# Filter.net
KiCad netlist of a schematic drawn in Altium Designer
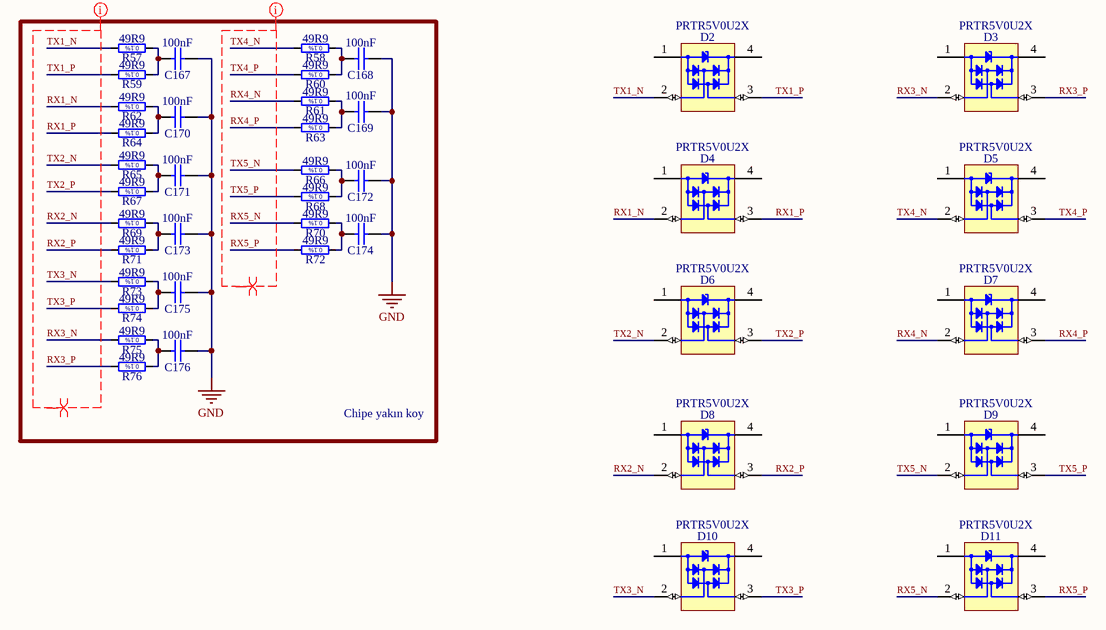
[diagram p0: Filter.SchDoc]

(export (version "E")
  (design (tool "Eeschema 10.0.6"))
  (components
    (comp (ref "C167")
      (value "100nF")
      (footprint "CAPC1608X87N")
      (description "Non-polarised capacitor")
      (fields
        (field (name "PART NUMBER") "CC0603_100NF_50V_10%_X7R")
        (field (name "VOLTAGE") "50V")
        (field (name "AUTHOR") "CERN DEM JLC")
      )
      (libsource (lib "Capacitors") (part "Capacitor - non polarized"))
    )
    (comp (ref "C168")
      (value "100nF")
      (footprint "CAPC1608X87N")
      (description "Non-polarised capacitor")
      (fields
        (field (name "PART NUMBER") "CC0603_100NF_50V_10%_X7R")
        (field (name "VOLTAGE") "50V")
        (field (name "AUTHOR") "CERN DEM JLC")
      )
      (libsource (lib "Capacitors") (part "Capacitor - non polarized"))
    )
    (comp (ref "C169")
      (value "100nF")
      (footprint "CAPC1608X87N")
      (description "Non-polarised capacitor")
      (fields
        (field (name "PART NUMBER") "CC0603_100NF_50V_10%_X7R")
        (field (name "VOLTAGE") "50V")
        (field (name "AUTHOR") "CERN DEM JLC")
      )
      (libsource (lib "Capacitors") (part "Capacitor - non polarized"))
    )
    (comp (ref "C170")
      (value "100nF")
      (footprint "CAPC1608X87N")
      (description "Non-polarised capacitor")
      (fields
        (field (name "PART NUMBER") "CC0603_100NF_50V_10%_X7R")
        (field (name "VOLTAGE") "50V")
        (field (name "AUTHOR") "CERN DEM JLC")
      )
      (libsource (lib "Capacitors") (part "Capacitor - non polarized"))
    )
    (comp (ref "C171")
      (value "100nF")
      (footprint "CAPC1608X87N")
      (description "Non-polarised capacitor")
      (fields
        (field (name "PART NUMBER") "CC0603_100NF_50V_10%_X7R")
        (field (name "VOLTAGE") "50V")
        (field (name "AUTHOR") "CERN DEM JLC")
      )
      (libsource (lib "Capacitors") (part "Capacitor - non polarized"))
    )
    (comp (ref "C172")
      (value "100nF")
      (footprint "CAPC1608X87N")
      (description "Non-polarised capacitor")
      (fields
        (field (name "PART NUMBER") "CC0603_100NF_50V_10%_X7R")
        (field (name "VOLTAGE") "50V")
        (field (name "AUTHOR") "CERN DEM JLC")
      )
      (libsource (lib "Capacitors") (part "Capacitor - non polarized"))
    )
    (comp (ref "C173")
      (value "100nF")
      (footprint "CAPC1608X87N")
      (description "Non-polarised capacitor")
      (fields
        (field (name "PART NUMBER") "CC0603_100NF_50V_10%_X7R")
        (field (name "VOLTAGE") "50V")
        (field (name "AUTHOR") "CERN DEM JLC")
      )
      (libsource (lib "Capacitors") (part "Capacitor - non polarized"))
    )
    (comp (ref "C174")
      (value "100nF")
      (footprint "CAPC1608X87N")
      (description "Non-polarised capacitor")
      (fields
        (field (name "PART NUMBER") "CC0603_100NF_50V_10%_X7R")
        (field (name "VOLTAGE") "50V")
        (field (name "AUTHOR") "CERN DEM JLC")
      )
      (libsource (lib "Capacitors") (part "Capacitor - non polarized"))
    )
    (comp (ref "C175")
      (value "100nF")
      (footprint "CAPC1608X87N")
      (description "Non-polarised capacitor")
      (fields
        (field (name "PART NUMBER") "CC0603_100NF_50V_10%_X7R")
        (field (name "VOLTAGE") "50V")
        (field (name "AUTHOR") "CERN DEM JLC")
      )
      (libsource (lib "Capacitors") (part "Capacitor - non polarized"))
    )
    (comp (ref "C176")
      (value "100nF")
      (footprint "CAPC1608X87N")
      (description "Non-polarised capacitor")
      (fields
        (field (name "PART NUMBER") "CC0603_100NF_50V_10%_X7R")
        (field (name "VOLTAGE") "50V")
        (field (name "AUTHOR") "CERN DEM JLC")
      )
      (libsource (lib "Capacitors") (part "Capacitor - non polarized"))
    )
    (comp (ref "D2")
      (value "PRTR5V0U2X")
      (footprint "SOT190P230X110-4N")
      (description "Ultra Low Capacitance Double Rail-to-Rail ESD Protection Diode")
      (fields
        (field (name "PART NUMBER") "PRTR5V0U2X")
        (field (name "VOLTAGE") "5.5V")
        (field (name "MANUFACTURER") "NXP Semiconductors")
        (field (name "AUTHOR") "CERN DEM JLC")
      )
      (libsource (lib "ICs And Semiconductors") (part "PRTR5V0U2X"))
    )
    (comp (ref "D3")
      (value "PRTR5V0U2X")
      (footprint "SOT190P230X110-4N")
      (description "Ultra Low Capacitance Double Rail-to-Rail ESD Protection Diode")
      (fields
        (field (name "PART NUMBER") "PRTR5V0U2X")
        (field (name "VOLTAGE") "5.5V")
        (field (name "MANUFACTURER") "NXP Semiconductors")
        (field (name "AUTHOR") "CERN DEM JLC")
      )
      (libsource (lib "ICs And Semiconductors") (part "PRTR5V0U2X"))
    )
    (comp (ref "D4")
      (value "PRTR5V0U2X")
      (footprint "SOT190P230X110-4N")
      (description "Ultra Low Capacitance Double Rail-to-Rail ESD Protection Diode")
      (fields
        (field (name "PART NUMBER") "PRTR5V0U2X")
        (field (name "VOLTAGE") "5.5V")
        (field (name "MANUFACTURER") "NXP Semiconductors")
        (field (name "AUTHOR") "CERN DEM JLC")
      )
      (libsource (lib "ICs And Semiconductors") (part "PRTR5V0U2X"))
    )
    (comp (ref "D5")
      (value "PRTR5V0U2X")
      (footprint "SOT190P230X110-4N")
      (description "Ultra Low Capacitance Double Rail-to-Rail ESD Protection Diode")
      (fields
        (field (name "PART NUMBER") "PRTR5V0U2X")
        (field (name "VOLTAGE") "5.5V")
        (field (name "MANUFACTURER") "NXP Semiconductors")
        (field (name "AUTHOR") "CERN DEM JLC")
      )
      (libsource (lib "ICs And Semiconductors") (part "PRTR5V0U2X"))
    )
    (comp (ref "D6")
      (value "PRTR5V0U2X")
      (footprint "SOT190P230X110-4N")
      (description "Ultra Low Capacitance Double Rail-to-Rail ESD Protection Diode")
      (fields
        (field (name "PART NUMBER") "PRTR5V0U2X")
        (field (name "VOLTAGE") "5.5V")
        (field (name "MANUFACTURER") "NXP Semiconductors")
        (field (name "AUTHOR") "CERN DEM JLC")
      )
      (libsource (lib "ICs And Semiconductors") (part "PRTR5V0U2X"))
    )
    (comp (ref "D7")
      (value "PRTR5V0U2X")
      (footprint "SOT190P230X110-4N")
      (description "Ultra Low Capacitance Double Rail-to-Rail ESD Protection Diode")
      (fields
        (field (name "PART NUMBER") "PRTR5V0U2X")
        (field (name "VOLTAGE") "5.5V")
        (field (name "MANUFACTURER") "NXP Semiconductors")
        (field (name "AUTHOR") "CERN DEM JLC")
      )
      (libsource (lib "ICs And Semiconductors") (part "PRTR5V0U2X"))
    )
    (comp (ref "D8")
      (value "PRTR5V0U2X")
      (footprint "SOT190P230X110-4N")
      (description "Ultra Low Capacitance Double Rail-to-Rail ESD Protection Diode")
      (fields
        (field (name "PART NUMBER") "PRTR5V0U2X")
        (field (name "VOLTAGE") "5.5V")
        (field (name "MANUFACTURER") "NXP Semiconductors")
        (field (name "AUTHOR") "CERN DEM JLC")
      )
      (libsource (lib "ICs And Semiconductors") (part "PRTR5V0U2X"))
    )
    (comp (ref "D9")
      (value "PRTR5V0U2X")
      (footprint "SOT190P230X110-4N")
      (description "Ultra Low Capacitance Double Rail-to-Rail ESD Protection Diode")
      (fields
        (field (name "PART NUMBER") "PRTR5V0U2X")
        (field (name "VOLTAGE") "5.5V")
        (field (name "MANUFACTURER") "NXP Semiconductors")
        (field (name "AUTHOR") "CERN DEM JLC")
      )
      (libsource (lib "ICs And Semiconductors") (part "PRTR5V0U2X"))
    )
    (comp (ref "D10")
      (value "PRTR5V0U2X")
      (footprint "SOT190P230X110-4N")
      (description "Ultra Low Capacitance Double Rail-to-Rail ESD Protection Diode")
      (fields
        (field (name "PART NUMBER") "PRTR5V0U2X")
        (field (name "VOLTAGE") "5.5V")
        (field (name "MANUFACTURER") "NXP Semiconductors")
        (field (name "AUTHOR") "CERN DEM JLC")
      )
      (libsource (lib "ICs And Semiconductors") (part "PRTR5V0U2X"))
    )
    (comp (ref "D11")
      (value "PRTR5V0U2X")
      (footprint "SOT190P230X110-4N")
      (description "Ultra Low Capacitance Double Rail-to-Rail ESD Protection Diode")
      (fields
        (field (name "PART NUMBER") "PRTR5V0U2X")
        (field (name "VOLTAGE") "5.5V")
        (field (name "MANUFACTURER") "NXP Semiconductors")
        (field (name "AUTHOR") "CERN DEM JLC")
      )
      (libsource (lib "ICs And Semiconductors") (part "PRTR5V0U2X"))
    )
    (comp (ref "R57")
      (value "49R9")
      (footprint "RESC1608X55N")
      (description "Resistor - 0.1%")
      (fields
        (field (name "PART NUMBER") "R0603_49R9_0.1%_0.063W_10PPM")
        (field (name "POWER") "0.063W")
        (field (name "AUTHOR") "CERN DEM JLC")
      )
      (libsource (lib "Resistors") (part "Resistor - 0.1%"))
    )
    (comp (ref "R58")
      (value "49R9")
      (footprint "RESC1608X55N")
      (description "Resistor - 0.1%")
      (fields
        (field (name "PART NUMBER") "R0603_49R9_0.1%_0.063W_10PPM")
        (field (name "POWER") "0.063W")
        (field (name "AUTHOR") "CERN DEM JLC")
      )
      (libsource (lib "Resistors") (part "Resistor - 0.1%"))
    )
    (comp (ref "R59")
      (value "49R9")
      (footprint "RESC1608X55N")
      (description "Resistor - 0.1%")
      (fields
        (field (name "PART NUMBER") "R0603_49R9_0.1%_0.063W_10PPM")
        (field (name "POWER") "0.063W")
        (field (name "AUTHOR") "CERN DEM JLC")
      )
      (libsource (lib "Resistors") (part "Resistor - 0.1%"))
    )
    (comp (ref "R60")
      (value "49R9")
      (footprint "RESC1608X55N")
      (description "Resistor - 0.1%")
      (fields
        (field (name "PART NUMBER") "R0603_49R9_0.1%_0.063W_10PPM")
        (field (name "POWER") "0.063W")
        (field (name "AUTHOR") "CERN DEM JLC")
      )
      (libsource (lib "Resistors") (part "Resistor - 0.1%"))
    )
    (comp (ref "R61")
      (value "49R9")
      (footprint "RESC1608X55N")
      (description "Resistor - 0.1%")
      (fields
        (field (name "PART NUMBER") "R0603_49R9_0.1%_0.063W_10PPM")
        (field (name "POWER") "0.063W")
        (field (name "AUTHOR") "CERN DEM JLC")
      )
      (libsource (lib "Resistors") (part "Resistor - 0.1%"))
    )
    (comp (ref "R62")
      (value "49R9")
      (footprint "RESC1608X55N")
      (description "Resistor - 0.1%")
      (fields
        (field (name "PART NUMBER") "R0603_49R9_0.1%_0.063W_10PPM")
        (field (name "POWER") "0.063W")
        (field (name "AUTHOR") "CERN DEM JLC")
      )
      (libsource (lib "Resistors") (part "Resistor - 0.1%"))
    )
    (comp (ref "R63")
      (value "49R9")
      (footprint "RESC1608X55N")
      (description "Resistor - 0.1%")
      (fields
        (field (name "PART NUMBER") "R0603_49R9_0.1%_0.063W_10PPM")
        (field (name "POWER") "0.063W")
        (field (name "AUTHOR") "CERN DEM JLC")
      )
      (libsource (lib "Resistors") (part "Resistor - 0.1%"))
    )
    (comp (ref "R64")
      (value "49R9")
      (footprint "RESC1608X55N")
      (description "Resistor - 0.1%")
      (fields
        (field (name "PART NUMBER") "R0603_49R9_0.1%_0.063W_10PPM")
        (field (name "POWER") "0.063W")
        (field (name "AUTHOR") "CERN DEM JLC")
      )
      (libsource (lib "Resistors") (part "Resistor - 0.1%"))
    )
    (comp (ref "R65")
      (value "49R9")
      (footprint "RESC1608X55N")
      (description "Resistor - 0.1%")
      (fields
        (field (name "PART NUMBER") "R0603_49R9_0.1%_0.063W_10PPM")
        (field (name "POWER") "0.063W")
        (field (name "AUTHOR") "CERN DEM JLC")
      )
      (libsource (lib "Resistors") (part "Resistor - 0.1%"))
    )
    (comp (ref "R66")
      (value "49R9")
      (footprint "RESC1608X55N")
      (description "Resistor - 0.1%")
      (fields
        (field (name "PART NUMBER") "R0603_49R9_0.1%_0.063W_10PPM")
        (field (name "POWER") "0.063W")
        (field (name "AUTHOR") "CERN DEM JLC")
      )
      (libsource (lib "Resistors") (part "Resistor - 0.1%"))
    )
    (comp (ref "R67")
      (value "49R9")
      (footprint "RESC1608X55N")
      (description "Resistor - 0.1%")
      (fields
        (field (name "PART NUMBER") "R0603_49R9_0.1%_0.063W_10PPM")
        (field (name "POWER") "0.063W")
        (field (name "AUTHOR") "CERN DEM JLC")
      )
      (libsource (lib "Resistors") (part "Resistor - 0.1%"))
    )
    (comp (ref "R68")
      (value "49R9")
      (footprint "RESC1608X55N")
      (description "Resistor - 0.1%")
      (fields
        (field (name "PART NUMBER") "R0603_49R9_0.1%_0.063W_10PPM")
        (field (name "POWER") "0.063W")
        (field (name "AUTHOR") "CERN DEM JLC")
      )
      (libsource (lib "Resistors") (part "Resistor - 0.1%"))
    )
    (comp (ref "R69")
      (value "49R9")
      (footprint "RESC1608X55N")
      (description "Resistor - 0.1%")
      (fields
        (field (name "PART NUMBER") "R0603_49R9_0.1%_0.063W_10PPM")
        (field (name "POWER") "0.063W")
        (field (name "AUTHOR") "CERN DEM JLC")
      )
      (libsource (lib "Resistors") (part "Resistor - 0.1%"))
    )
    (comp (ref "R70")
      (value "49R9")
      (footprint "RESC1608X55N")
      (description "Resistor - 0.1%")
      (fields
        (field (name "PART NUMBER") "R0603_49R9_0.1%_0.063W_10PPM")
        (field (name "POWER") "0.063W")
        (field (name "AUTHOR") "CERN DEM JLC")
      )
      (libsource (lib "Resistors") (part "Resistor - 0.1%"))
    )
    (comp (ref "R71")
      (value "49R9")
      (footprint "RESC1608X55N")
      (description "Resistor - 0.1%")
      (fields
        (field (name "PART NUMBER") "R0603_49R9_0.1%_0.063W_10PPM")
        (field (name "POWER") "0.063W")
        (field (name "AUTHOR") "CERN DEM JLC")
      )
      (libsource (lib "Resistors") (part "Resistor - 0.1%"))
    )
    (comp (ref "R72")
      (value "49R9")
      (footprint "RESC1608X55N")
      (description "Resistor - 0.1%")
      (fields
        (field (name "PART NUMBER") "R0603_49R9_0.1%_0.063W_10PPM")
        (field (name "POWER") "0.063W")
        (field (name "AUTHOR") "CERN DEM JLC")
      )
      (libsource (lib "Resistors") (part "Resistor - 0.1%"))
    )
    (comp (ref "R73")
      (value "49R9")
      (footprint "RESC1608X55N")
      (description "Resistor - 0.1%")
      (fields
        (field (name "PART NUMBER") "R0603_49R9_0.1%_0.063W_10PPM")
        (field (name "POWER") "0.063W")
        (field (name "AUTHOR") "CERN DEM JLC")
      )
      (libsource (lib "Resistors") (part "Resistor - 0.1%"))
    )
    (comp (ref "R74")
      (value "49R9")
      (footprint "RESC1608X55N")
      (description "Resistor - 0.1%")
      (fields
        (field (name "PART NUMBER") "R0603_49R9_0.1%_0.063W_10PPM")
        (field (name "POWER") "0.063W")
        (field (name "AUTHOR") "CERN DEM JLC")
      )
      (libsource (lib "Resistors") (part "Resistor - 0.1%"))
    )
    (comp (ref "R75")
      (value "49R9")
      (footprint "RESC1608X55N")
      (description "Resistor - 0.1%")
      (fields
        (field (name "PART NUMBER") "R0603_49R9_0.1%_0.063W_10PPM")
        (field (name "POWER") "0.063W")
        (field (name "AUTHOR") "CERN DEM JLC")
      )
      (libsource (lib "Resistors") (part "Resistor - 0.1%"))
    )
    (comp (ref "R76")
      (value "49R9")
      (footprint "RESC1608X55N")
      (description "Resistor - 0.1%")
      (fields
        (field (name "PART NUMBER") "R0603_49R9_0.1%_0.063W_10PPM")
        (field (name "POWER") "0.063W")
        (field (name "AUTHOR") "CERN DEM JLC")
      )
      (libsource (lib "Resistors") (part "Resistor - 0.1%"))
    )
  )
  (nets
    (net (code "1") (name "/RX1_N") (class "Default")
      (node (ref "D4") (pin "2") (pinfunction "I/O1_2") (pintype "bidirectional"))
      (node (ref "R62") (pin "2") (pinfunction "2_2") (pintype "passive"))
    )
    (net (code "2") (name "/RX1_P") (class "Default")
      (node (ref "D4") (pin "3") (pinfunction "I/O2_3") (pintype "bidirectional"))
      (node (ref "R64") (pin "2") (pinfunction "2_2") (pintype "passive"))
    )
    (net (code "3") (name "/RX2_N") (class "Default")
      (node (ref "D8") (pin "2") (pinfunction "I/O1_2") (pintype "bidirectional"))
      (node (ref "R69") (pin "2") (pinfunction "2_2") (pintype "passive"))
    )
    (net (code "4") (name "/RX2_P") (class "Default")
      (node (ref "D8") (pin "3") (pinfunction "I/O2_3") (pintype "bidirectional"))
      (node (ref "R71") (pin "2") (pinfunction "2_2") (pintype "passive"))
    )
    (net (code "5") (name "/RX3_N") (class "Default")
      (node (ref "D3") (pin "2") (pinfunction "I/O1_2") (pintype "bidirectional"))
      (node (ref "R75") (pin "2") (pinfunction "2_2") (pintype "passive"))
    )
    (net (code "6") (name "/RX3_P") (class "Default")
      (node (ref "D3") (pin "3") (pinfunction "I/O2_3") (pintype "bidirectional"))
      (node (ref "R76") (pin "2") (pinfunction "2_2") (pintype "passive"))
    )
    (net (code "7") (name "/RX4_N") (class "Default")
      (node (ref "D7") (pin "2") (pinfunction "I/O1_2") (pintype "bidirectional"))
      (node (ref "R61") (pin "2") (pinfunction "2_2") (pintype "passive"))
    )
    (net (code "8") (name "/RX4_P") (class "Default")
      (node (ref "D7") (pin "3") (pinfunction "I/O2_3") (pintype "bidirectional"))
      (node (ref "R63") (pin "2") (pinfunction "2_2") (pintype "passive"))
    )
    (net (code "9") (name "/RX5_N") (class "Default")
      (node (ref "D11") (pin "2") (pinfunction "I/O1_2") (pintype "bidirectional"))
      (node (ref "R70") (pin "2") (pinfunction "2_2") (pintype "passive"))
    )
    (net (code "10") (name "/RX5_P") (class "Default")
      (node (ref "D11") (pin "3") (pinfunction "I/O2_3") (pintype "bidirectional"))
      (node (ref "R72") (pin "2") (pinfunction "2_2") (pintype "passive"))
    )
    (net (code "11") (name "/TX1_N") (class "Default")
      (node (ref "D2") (pin "2") (pinfunction "I/O1_2") (pintype "bidirectional"))
      (node (ref "R57") (pin "2") (pinfunction "2_2") (pintype "passive"))
    )
    (net (code "12") (name "/TX1_P") (class "Default")
      (node (ref "D2") (pin "3") (pinfunction "I/O2_3") (pintype "bidirectional"))
      (node (ref "R59") (pin "2") (pinfunction "2_2") (pintype "passive"))
    )
    (net (code "13") (name "/TX2_N") (class "Default")
      (node (ref "D6") (pin "2") (pinfunction "I/O1_2") (pintype "bidirectional"))
      (node (ref "R65") (pin "2") (pinfunction "2_2") (pintype "passive"))
    )
    (net (code "14") (name "/TX2_P") (class "Default")
      (node (ref "D6") (pin "3") (pinfunction "I/O2_3") (pintype "bidirectional"))
      (node (ref "R67") (pin "2") (pinfunction "2_2") (pintype "passive"))
    )
    (net (code "15") (name "/TX3_N") (class "Default")
      (node (ref "D10") (pin "2") (pinfunction "I/O1_2") (pintype "bidirectional"))
      (node (ref "R73") (pin "2") (pinfunction "2_2") (pintype "passive"))
    )
    (net (code "16") (name "/TX3_P") (class "Default")
      (node (ref "D10") (pin "3") (pinfunction "I/O2_3") (pintype "bidirectional"))
      (node (ref "R74") (pin "2") (pinfunction "2_2") (pintype "passive"))
    )
    (net (code "17") (name "/TX4_N") (class "Default")
      (node (ref "D5") (pin "2") (pinfunction "I/O1_2") (pintype "bidirectional"))
      (node (ref "R58") (pin "2") (pinfunction "2_2") (pintype "passive"))
    )
    (net (code "18") (name "/TX4_P") (class "Default")
      (node (ref "D5") (pin "3") (pinfunction "I/O2_3") (pintype "bidirectional"))
      (node (ref "R60") (pin "2") (pinfunction "2_2") (pintype "passive"))
    )
    (net (code "19") (name "/TX5_N") (class "Default")
      (node (ref "D9") (pin "2") (pinfunction "I/O1_2") (pintype "bidirectional"))
      (node (ref "R66") (pin "2") (pinfunction "2_2") (pintype "passive"))
    )
    (net (code "20") (name "/TX5_P") (class "Default")
      (node (ref "D9") (pin "3") (pinfunction "I/O2_3") (pintype "bidirectional"))
      (node (ref "R68") (pin "2") (pinfunction "2_2") (pintype "passive"))
    )
    (net (code "21") (name "GND") (class "Default")
      (node (ref "C167") (pin "1") (pinfunction "1_1") (pintype "passive"))
      (node (ref "C168") (pin "1") (pinfunction "1_1") (pintype "passive"))
      (node (ref "C169") (pin "1") (pinfunction "1_1") (pintype "passive"))
      (node (ref "C170") (pin "1") (pinfunction "1_1") (pintype "passive"))
      (node (ref "C171") (pin "1") (pinfunction "1_1") (pintype "passive"))
      (node (ref "C172") (pin "1") (pinfunction "1_1") (pintype "passive"))
      (node (ref "C173") (pin "1") (pinfunction "1_1") (pintype "passive"))
      (node (ref "C174") (pin "1") (pinfunction "1_1") (pintype "passive"))
      (node (ref "C175") (pin "1") (pinfunction "1_1") (pintype "passive"))
      (node (ref "C176") (pin "1") (pinfunction "1_1") (pintype "passive"))
    )
    (net (code "22") (name "Net-(C167-Pad2)") (class "Default")
      (node (ref "C167") (pin "2") (pinfunction "2_2") (pintype "passive"))
      (node (ref "R57") (pin "1") (pinfunction "1_1") (pintype "passive"))
      (node (ref "R59") (pin "1") (pinfunction "1_1") (pintype "passive"))
    )
    (net (code "23") (name "Net-(C168-Pad2)") (class "Default")
      (node (ref "C168") (pin "2") (pinfunction "2_2") (pintype "passive"))
      (node (ref "R58") (pin "1") (pinfunction "1_1") (pintype "passive"))
      (node (ref "R60") (pin "1") (pinfunction "1_1") (pintype "passive"))
    )
    (net (code "24") (name "Net-(C169-Pad2)") (class "Default")
      (node (ref "C169") (pin "2") (pinfunction "2_2") (pintype "passive"))
      (node (ref "R61") (pin "1") (pinfunction "1_1") (pintype "passive"))
      (node (ref "R63") (pin "1") (pinfunction "1_1") (pintype "passive"))
    )
    (net (code "25") (name "Net-(C170-Pad2)") (class "Default")
      (node (ref "C170") (pin "2") (pinfunction "2_2") (pintype "passive"))
      (node (ref "R62") (pin "1") (pinfunction "1_1") (pintype "passive"))
      (node (ref "R64") (pin "1") (pinfunction "1_1") (pintype "passive"))
    )
    (net (code "26") (name "Net-(C171-Pad2)") (class "Default")
      (node (ref "C171") (pin "2") (pinfunction "2_2") (pintype "passive"))
      (node (ref "R65") (pin "1") (pinfunction "1_1") (pintype "passive"))
      (node (ref "R67") (pin "1") (pinfunction "1_1") (pintype "passive"))
    )
    (net (code "27") (name "Net-(C172-Pad2)") (class "Default")
      (node (ref "C172") (pin "2") (pinfunction "2_2") (pintype "passive"))
      (node (ref "R66") (pin "1") (pinfunction "1_1") (pintype "passive"))
      (node (ref "R68") (pin "1") (pinfunction "1_1") (pintype "passive"))
    )
    (net (code "28") (name "Net-(C173-Pad2)") (class "Default")
      (node (ref "C173") (pin "2") (pinfunction "2_2") (pintype "passive"))
      (node (ref "R69") (pin "1") (pinfunction "1_1") (pintype "passive"))
      (node (ref "R71") (pin "1") (pinfunction "1_1") (pintype "passive"))
    )
    (net (code "29") (name "Net-(C174-Pad2)") (class "Default")
      (node (ref "C174") (pin "2") (pinfunction "2_2") (pintype "passive"))
      (node (ref "R70") (pin "1") (pinfunction "1_1") (pintype "passive"))
      (node (ref "R72") (pin "1") (pinfunction "1_1") (pintype "passive"))
    )
    (net (code "30") (name "Net-(C175-Pad2)") (class "Default")
      (node (ref "C175") (pin "2") (pinfunction "2_2") (pintype "passive"))
      (node (ref "R73") (pin "1") (pinfunction "1_1") (pintype "passive"))
      (node (ref "R74") (pin "1") (pinfunction "1_1") (pintype "passive"))
    )
    (net (code "31") (name "Net-(C176-Pad2)") (class "Default")
      (node (ref "C176") (pin "2") (pinfunction "2_2") (pintype "passive"))
      (node (ref "R75") (pin "1") (pinfunction "1_1") (pintype "passive"))
      (node (ref "R76") (pin "1") (pinfunction "1_1") (pintype "passive"))
    )
    (net (code "32") (name "unconnected-(D2-GND-Pad1)") (class "Default")
      (node (ref "D2") (pin "1") (pinfunction "GND_1") (pintype "power_in"))
    )
    (net (code "33") (name "unconnected-(D2-VCC-Pad4)") (class "Default")
      (node (ref "D2") (pin "4") (pinfunction "VCC_4") (pintype "power_in"))
    )
    (net (code "34") (name "unconnected-(D3-GND-Pad1)") (class "Default")
      (node (ref "D3") (pin "1") (pinfunction "GND_1") (pintype "power_in"))
    )
    (net (code "35") (name "unconnected-(D3-VCC-Pad4)") (class "Default")
      (node (ref "D3") (pin "4") (pinfunction "VCC_4") (pintype "power_in"))
    )
    (net (code "36") (name "unconnected-(D4-GND-Pad1)") (class "Default")
      (node (ref "D4") (pin "1") (pinfunction "GND_1") (pintype "power_in"))
    )
    (net (code "37") (name "unconnected-(D4-VCC-Pad4)") (class "Default")
      (node (ref "D4") (pin "4") (pinfunction "VCC_4") (pintype "power_in"))
    )
    (net (code "38") (name "unconnected-(D5-GND-Pad1)") (class "Default")
      (node (ref "D5") (pin "1") (pinfunction "GND_1") (pintype "power_in"))
    )
    (net (code "39") (name "unconnected-(D5-VCC-Pad4)") (class "Default")
      (node (ref "D5") (pin "4") (pinfunction "VCC_4") (pintype "power_in"))
    )
    (net (code "40") (name "unconnected-(D6-GND-Pad1)") (class "Default")
      (node (ref "D6") (pin "1") (pinfunction "GND_1") (pintype "power_in"))
    )
    (net (code "41") (name "unconnected-(D6-VCC-Pad4)") (class "Default")
      (node (ref "D6") (pin "4") (pinfunction "VCC_4") (pintype "power_in"))
    )
    (net (code "42") (name "unconnected-(D7-GND-Pad1)") (class "Default")
      (node (ref "D7") (pin "1") (pinfunction "GND_1") (pintype "power_in"))
    )
    (net (code "43") (name "unconnected-(D7-VCC-Pad4)") (class "Default")
      (node (ref "D7") (pin "4") (pinfunction "VCC_4") (pintype "power_in"))
    )
    (net (code "44") (name "unconnected-(D8-GND-Pad1)") (class "Default")
      (node (ref "D8") (pin "1") (pinfunction "GND_1") (pintype "power_in"))
    )
    (net (code "45") (name "unconnected-(D8-VCC-Pad4)") (class "Default")
      (node (ref "D8") (pin "4") (pinfunction "VCC_4") (pintype "power_in"))
    )
    (net (code "46") (name "unconnected-(D9-GND-Pad1)") (class "Default")
      (node (ref "D9") (pin "1") (pinfunction "GND_1") (pintype "power_in"))
    )
    (net (code "47") (name "unconnected-(D9-VCC-Pad4)") (class "Default")
      (node (ref "D9") (pin "4") (pinfunction "VCC_4") (pintype "power_in"))
    )
    (net (code "48") (name "unconnected-(D10-GND-Pad1)") (class "Default")
      (node (ref "D10") (pin "1") (pinfunction "GND_1") (pintype "power_in"))
    )
    (net (code "49") (name "unconnected-(D10-VCC-Pad4)") (class "Default")
      (node (ref "D10") (pin "4") (pinfunction "VCC_4") (pintype "power_in"))
    )
    (net (code "50") (name "unconnected-(D11-GND-Pad1)") (class "Default")
      (node (ref "D11") (pin "1") (pinfunction "GND_1") (pintype "power_in"))
    )
    (net (code "51") (name "unconnected-(D11-VCC-Pad4)") (class "Default")
      (node (ref "D11") (pin "4") (pinfunction "VCC_4") (pintype "power_in"))
    )
  )
)
